# RTC.net
KiCad netlist of a schematic drawn in Altium Designer
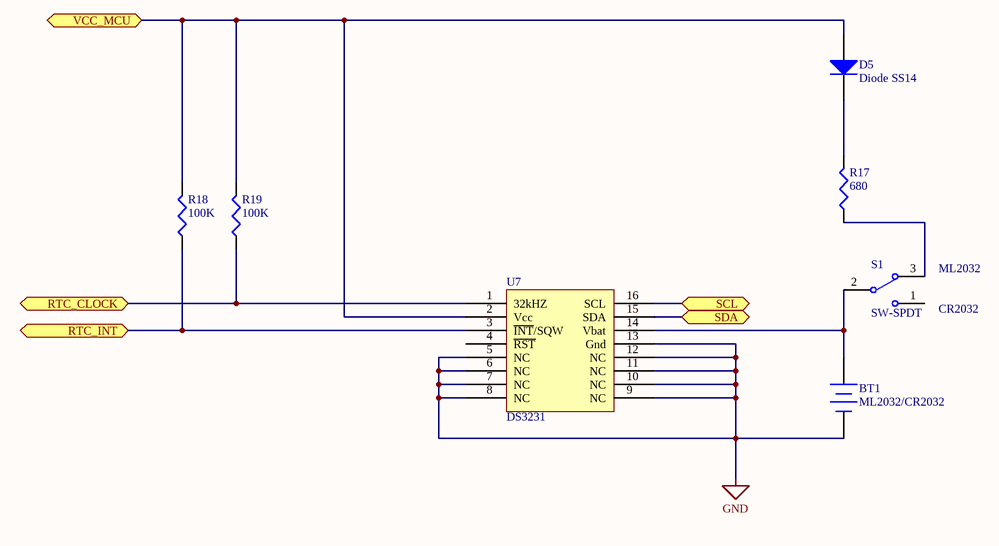
[diagram p0: RTC.SchDoc]

(export (version "E")
  (design (tool "Eeschema 10.0.6"))
  (components
    (comp (ref "BT1")
      (value "ML2032/CR2032")
      (footprint "clock:BAT2025-2032")
      (description "Multicell Battery")
      (fields (field (name "PUBLISHER") "Altium Limited"))
      (libsource (lib "Miscellaneous Devices") (part "Battery"))
    )
    (comp (ref "D5")
      (value "Diode SS14")
      (footprint "clock:SMA")
      (description "1 Amp General Purpose Rectifier")
      (fields (field (name "PUBLISHER") "Altium Limited"))
      (libsource (lib "Miscellaneous Devices") (part "Diode 1N4005"))
    )
    (comp (ref "R17")
      (value "680")
      (footprint "clock:0603")
      (description "Resistor")
      (fields (field (name "Comment") "Res3") (field (name "PUBLISHER") "Altium Limited"))
      (libsource (lib "Miscellaneous Devices") (part "Res3"))
    )
    (comp (ref "R18")
      (value "100K")
      (footprint "clock:0603")
      (description "Resistor")
      (fields (field (name "Comment") "Res3") (field (name "PUBLISHER") "Altium Limited"))
      (libsource (lib "Miscellaneous Devices") (part "Res3"))
    )
    (comp (ref "R19")
      (value "100K")
      (footprint "clock:0603")
      (description "Resistor")
      (fields (field (name "Comment") "Res3") (field (name "PUBLISHER") "Altium Limited"))
      (libsource (lib "Miscellaneous Devices") (part "Res3"))
    )
    (comp (ref "S1")
      (value "SW-SPDT")
      (footprint "clock:SW-SPDT")
      (description "SPDT Subminiature Toggle Switch, Right Angle Mounting, Vertical Actuation")
      (fields (field (name "PUBLISHER") "Altium Limited"))
      (libsource (lib "Miscellaneous Devices") (part "SW-SPDT"))
    )
    (comp (ref "U7") (value "DS3231") (footprint "clock:WSO16_M") (libsource (lib "clock") (part "DS3231")))
  )
  (nets
    (net (code "1") (name "/RTC_CLOCK") (class "Default")
      (node (ref "R19") (pin "1") (pinfunction "1_1") (pintype "passive"))
      (node (ref "U7") (pin "1") (pinfunction "32kHZ_1") (pintype "passive"))
    )
    (net (code "2") (name "/RTC_INT") (class "Default")
      (node (ref "R18") (pin "1") (pinfunction "1_1") (pintype "passive"))
      (node (ref "U7") (pin "3") (pinfunction "~{INT}/SQW_3") (pintype "passive"))
    )
    (net (code "3") (name "/SCL") (class "Default")
      (node (ref "U7") (pin "16") (pinfunction "SCL_16") (pintype "passive"))
    )
    (net (code "4") (name "/SDA") (class "Default")
      (node (ref "U7") (pin "15") (pinfunction "SDA_15") (pintype "passive"))
    )
    (net (code "5") (name "/VCC_MCU") (class "Default")
      (node (ref "D5") (pin "1") (pinfunction "A_1") (pintype "passive"))
      (node (ref "R18") (pin "2") (pinfunction "2_2") (pintype "passive"))
      (node (ref "R19") (pin "2") (pinfunction "2_2") (pintype "passive"))
      (node (ref "U7") (pin "2") (pinfunction "Vcc_2") (pintype "passive"))
    )
    (net (code "6") (name "GND") (class "Default")
      (node (ref "BT1") (pin "2") (pinfunction "-_2") (pintype "passive"))
      (node (ref "U7") (pin "10") (pinfunction "NC_10") (pintype "passive"))
      (node (ref "U7") (pin "11") (pinfunction "NC_11") (pintype "passive"))
      (node (ref "U7") (pin "12") (pinfunction "NC_12") (pintype "passive"))
      (node (ref "U7") (pin "13") (pinfunction "Gnd_13") (pintype "passive"))
      (node (ref "U7") (pin "5") (pinfunction "NC_5") (pintype "passive"))
      (node (ref "U7") (pin "6") (pinfunction "NC_6") (pintype "passive"))
      (node (ref "U7") (pin "7") (pinfunction "NC_7") (pintype "passive"))
      (node (ref "U7") (pin "8") (pinfunction "NC_8") (pintype "passive"))
      (node (ref "U7") (pin "9") (pinfunction "NC_9") (pintype "passive"))
    )
    (net (code "7") (name "Net-(BT1-+)") (class "Default")
      (node (ref "BT1") (pin "1") (pinfunction "+_1") (pintype "passive"))
      (node (ref "S1") (pin "2") (pinfunction "2_2") (pintype "passive"))
      (node (ref "U7") (pin "14") (pinfunction "Vbat_14") (pintype "passive"))
    )
    (net (code "8") (name "Net-(D5-K)") (class "Default")
      (node (ref "D5") (pin "2") (pinfunction "K_2") (pintype "passive"))
      (node (ref "R17") (pin "2") (pinfunction "2_2") (pintype "passive"))
    )
    (net (code "9") (name "Net-(R17-Pad1)") (class "Default")
      (node (ref "R17") (pin "1") (pinfunction "1_1") (pintype "passive"))
      (node (ref "S1") (pin "3") (pinfunction "3_3") (pintype "passive"))
    )
    (net (code "10") (name "unconnected-(S1-Pad1)") (class "Default")
      (node (ref "S1") (pin "1") (pinfunction "1_1") (pintype "passive"))
    )
    (net (code "11") (name "unconnected-(U7-~{RST}-Pad4)") (class "Default")
      (node (ref "U7") (pin "4") (pinfunction "~{RST}_4") (pintype "passive"))
    )
  )
)
